# smps_test.net
KiCad netlist of a schematic drawn in EAGLE
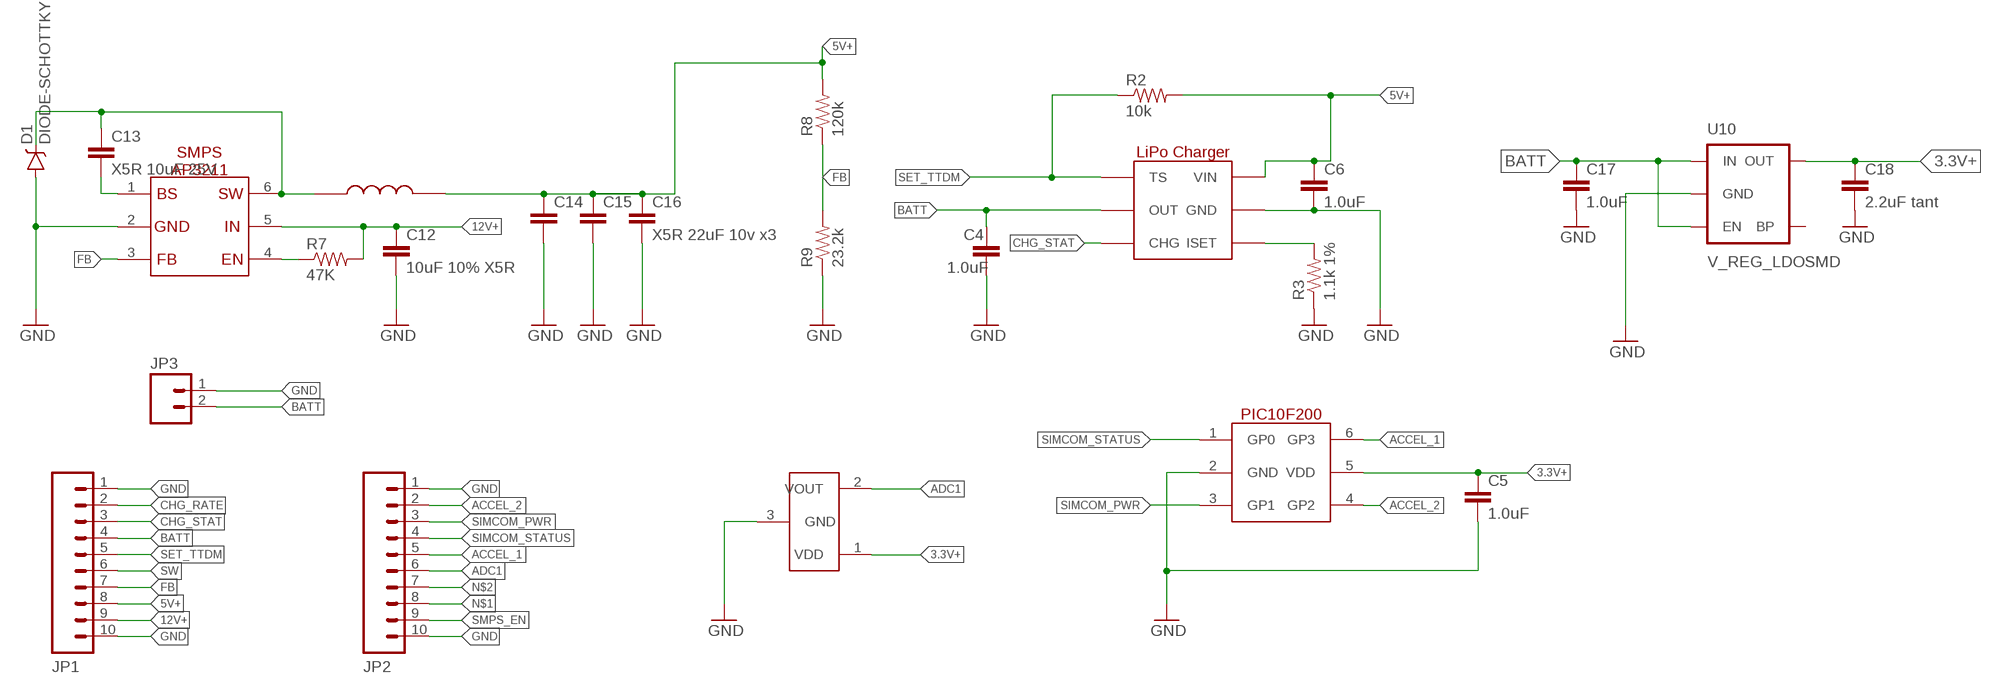
[diagram p0: schematic, sheet 1]

(export (version "E")
  (design (tool "Eeschema 10.0.6"))
  (components
    (comp (ref "C4")
      (value "1.0uF")
      (footprint "eagle-import:0603-CAP")
      (libsource (lib "eagle-import") (part "1.0UF-16V-10%(0603)"))
    )
    (comp (ref "C5")
      (value "1.0uF")
      (footprint "eagle-import:0603-CAP")
      (libsource (lib "eagle-import") (part "1.0UF-16V-10%(0603)"))
    )
    (comp (ref "C6")
      (value "1.0uF")
      (footprint "eagle-import:0603-CAP")
      (libsource (lib "eagle-import") (part "1.0UF-16V-10%(0603)"))
    )
    (comp (ref "C12")
      (value "10uF 10% X5R")
      (footprint "eagle-import:1206")
      (libsource (lib "eagle-import") (part "CAP1206"))
    )
    (comp (ref "C13")
      (value "X5R 10uF 25V")
      (footprint "eagle-import:0603-CAP")
      (libsource (lib "eagle-import") (part "CAP0603-CAP"))
    )
    (comp (ref "C14")
      (value "CAP0603-CAP")
      (footprint "eagle-import:0603-CAP")
      (libsource (lib "eagle-import") (part "CAP0603-CAP"))
    )
    (comp (ref "C15")
      (value "CAP0603-CAP")
      (footprint "eagle-import:0603-CAP")
      (libsource (lib "eagle-import") (part "CAP0603-CAP"))
    )
    (comp (ref "C16")
      (value "X5R 22uF 10v x3")
      (footprint "eagle-import:0603-CAP")
      (libsource (lib "eagle-import") (part "CAP0603-CAP"))
    )
    (comp (ref "C17")
      (value "1.0uF")
      (footprint "eagle-import:0603-CAP")
      (libsource (lib "eagle-import") (part "CAP0603-CAP"))
    )
    (comp (ref "C18")
      (value "2.2uF tant")
      (footprint "eagle-import:0603-CAP")
      (libsource (lib "eagle-import") (part "CAP0603-CAP"))
    )
    (comp (ref "D1")
      (value "DIODE-SCHOTTKY")
      (footprint "eagle-import:MICRO_SMP")
      (libsource (lib "eagle-import") (part "DIODE-SCHOTTKY"))
    )
    (comp (ref "JP1")
      (value "M10LOCK")
      (footprint "eagle-import:1X10_LOCK")
      (libsource (lib "eagle-import") (part "M10LOCK"))
    )
    (comp (ref "JP2")
      (value "M10LOCK")
      (footprint "eagle-import:1X10_LOCK")
      (libsource (lib "eagle-import") (part "M10LOCK"))
    )
    (comp (ref "JP3")
      (value "M02-JST-2MM-SMT")
      (footprint "eagle-import:JST-2-SMD")
      (libsource (lib "eagle-import") (part "M02-JST-2MM-SMT"))
    )
    (comp (ref "R2")
      (value "10k")
      (footprint "eagle-import:0603-RES")
      (libsource (lib "eagle-import") (part "RESISTOR0603-RES"))
    )
    (comp (ref "R3")
      (value "1.1k 1%")
      (footprint "eagle-import:0603-RES")
      (libsource (lib "eagle-import") (part "RESISTOR0603-RES"))
    )
    (comp (ref "R7")
      (value "47K")
      (footprint "eagle-import:0603-RES")
      (libsource (lib "eagle-import") (part "47KOHM1/10W1%(0603)"))
    )
    (comp (ref "R8")
      (value "120k")
      (footprint "eagle-import:0603-RES")
      (libsource (lib "eagle-import") (part "RESISTOR0603"))
    )
    (comp (ref "R9")
      (value "23.2k")
      (footprint "eagle-import:0603-RES")
      (libsource (lib "eagle-import") (part "RESISTOR0603"))
    )
    (comp (ref "U$1")
      (value "MCP9700T-E")
      (footprint "eagle-import:SOT23-3")
      (libsource (lib "eagle-import") (part "MCP9700T-E"))
    )
    (comp (ref "U$2")
      (value "AP3211")
      (footprint "eagle-import:SOT23-6")
      (libsource (lib "eagle-import") (part "AP3211"))
    )
    (comp (ref "U$4")
      (value "INDUCTOR")
      (footprint "eagle-import:INDUCTOR_FIXED")
      (libsource (lib "eagle-import") (part "INDUCTOR"))
    )
    (comp (ref "U3")
      (value "BQ21040")
      (footprint "eagle-import:SOT23-6")
      (libsource (lib "eagle-import") (part "BQ21040"))
    )
    (comp (ref "U6")
      (value "PIC10F200")
      (footprint "eagle-import:SOT23-6")
      (libsource (lib "eagle-import") (part "PIC10F200"))
    )
    (comp (ref "U10")
      (value "V_REG_LDOSMD")
      (footprint "eagle-import:SOT23-5")
      (libsource (lib "eagle-import") (part "V_REG_LDOSMD"))
    )
  )
  (nets
    (net (code "1") (name "3.3V+") (class "Default")
      (node (ref "C18") (pin "1") (pinfunction "1_1") (pintype "passive"))
      (node (ref "C5") (pin "1") (pinfunction "1_1") (pintype "passive"))
      (node (ref "U$1") (pin "1") (pinfunction "VDD_1") (pintype "bidirectional"))
      (node (ref "U10") (pin "5") (pinfunction "OUT_5") (pintype "passive"))
      (node (ref "U6") (pin "5") (pinfunction "VDD_5") (pintype "bidirectional"))
    )
    (net (code "2") (name "5V+") (class "Default")
      (node (ref "C14") (pin "1") (pinfunction "1_1") (pintype "passive"))
      (node (ref "C15") (pin "1") (pinfunction "1_1") (pintype "passive"))
      (node (ref "C16") (pin "1") (pinfunction "1_1") (pintype "passive"))
      (node (ref "C6") (pin "1") (pinfunction "1_1") (pintype "passive"))
      (node (ref "JP1") (pin "8") (pinfunction "8_8") (pintype "passive"))
      (node (ref "R2") (pin "2") (pinfunction "2_2") (pintype "passive"))
      (node (ref "R8") (pin "2") (pinfunction "2_2") (pintype "passive"))
      (node (ref "U$4") (pin "P$2") (pinfunction "P$2_P$2") (pintype "bidirectional"))
      (node (ref "U3") (pin "6") (pinfunction "VIN_6") (pintype "bidirectional"))
    )
    (net (code "3") (name "12V+") (class "Default")
      (node (ref "C12") (pin "1") (pinfunction "1_1") (pintype "passive"))
      (node (ref "JP1") (pin "9") (pinfunction "9_9") (pintype "passive"))
      (node (ref "R7") (pin "2") (pinfunction "2_2") (pintype "passive"))
      (node (ref "U$2") (pin "5") (pinfunction "P$5_5") (pintype "bidirectional"))
    )
    (net (code "4") (name "ACCEL_1") (class "Default")
      (node (ref "JP2") (pin "5") (pinfunction "5_5") (pintype "passive"))
      (node (ref "U6") (pin "6") (pinfunction "GP3_6") (pintype "bidirectional"))
    )
    (net (code "5") (name "ACCEL_2") (class "Default")
      (node (ref "JP2") (pin "2") (pinfunction "2_2") (pintype "passive"))
      (node (ref "U6") (pin "4") (pinfunction "GP2_4") (pintype "bidirectional"))
    )
    (net (code "6") (name "ADC1") (class "Default")
      (node (ref "JP2") (pin "6") (pinfunction "6_6") (pintype "passive"))
      (node (ref "U$1") (pin "2") (pinfunction "VOUT_2") (pintype "bidirectional"))
    )
    (net (code "7") (name "BATT") (class "Default")
      (node (ref "C17") (pin "1") (pinfunction "1_1") (pintype "passive"))
      (node (ref "C4") (pin "1") (pinfunction "1_1") (pintype "passive"))
      (node (ref "JP1") (pin "4") (pinfunction "4_4") (pintype "passive"))
      (node (ref "JP3") (pin "2") (pinfunction "1_2") (pintype "passive"))
      (node (ref "U10") (pin "1") (pinfunction "IN_1") (pintype "input"))
      (node (ref "U10") (pin "3") (pinfunction "EN_3") (pintype "input"))
      (node (ref "U3") (pin "2") (pinfunction "OUT_2") (pintype "bidirectional"))
    )
    (net (code "8") (name "CHG_RATE") (class "Default")
      (node (ref "JP1") (pin "2") (pinfunction "2_2") (pintype "passive"))
      (node (ref "R3") (pin "2") (pinfunction "2_2") (pintype "passive"))
      (node (ref "U3") (pin "4") (pinfunction "ISET_4") (pintype "bidirectional"))
    )
    (net (code "9") (name "CHG_STAT") (class "Default")
      (node (ref "JP1") (pin "3") (pinfunction "3_3") (pintype "passive"))
      (node (ref "U3") (pin "3") (pinfunction "CHG_3") (pintype "bidirectional"))
    )
    (net (code "10") (name "FB") (class "Default")
      (node (ref "JP1") (pin "7") (pinfunction "7_7") (pintype "passive"))
      (node (ref "R8") (pin "1") (pinfunction "1_1") (pintype "passive"))
      (node (ref "R9") (pin "2") (pinfunction "2_2") (pintype "passive"))
      (node (ref "U$2") (pin "3") (pinfunction "P$3_3") (pintype "bidirectional"))
    )
    (net (code "11") (name "GND") (class "Default")
      (node (ref "C12") (pin "2") (pinfunction "2_2") (pintype "passive"))
      (node (ref "C14") (pin "2") (pinfunction "2_2") (pintype "passive"))
      (node (ref "C15") (pin "2") (pinfunction "2_2") (pintype "passive"))
      (node (ref "C16") (pin "2") (pinfunction "2_2") (pintype "passive"))
      (node (ref "C17") (pin "2") (pinfunction "2_2") (pintype "passive"))
      (node (ref "C18") (pin "2") (pinfunction "2_2") (pintype "passive"))
      (node (ref "C4") (pin "2") (pinfunction "2_2") (pintype "passive"))
      (node (ref "C5") (pin "2") (pinfunction "2_2") (pintype "passive"))
      (node (ref "C6") (pin "2") (pinfunction "2_2") (pintype "passive"))
      (node (ref "D1") (pin "P$2") (pinfunction "A_P$2") (pintype "passive"))
      (node (ref "JP1") (pin "1") (pinfunction "1_1") (pintype "passive"))
      (node (ref "JP1") (pin "10") (pinfunction "10_10") (pintype "passive"))
      (node (ref "JP2") (pin "1") (pinfunction "1_1") (pintype "passive"))
      (node (ref "JP2") (pin "10") (pinfunction "10_10") (pintype "passive"))
      (node (ref "JP3") (pin "1") (pinfunction "2_1") (pintype "passive"))
      (node (ref "R3") (pin "1") (pinfunction "1_1") (pintype "passive"))
      (node (ref "R9") (pin "1") (pinfunction "1_1") (pintype "passive"))
      (node (ref "U$1") (pin "3") (pinfunction "GND_3") (pintype "bidirectional"))
      (node (ref "U$2") (pin "2") (pinfunction "P$2_2") (pintype "bidirectional"))
      (node (ref "U10") (pin "2") (pinfunction "GND_2") (pintype "input"))
      (node (ref "U3") (pin "5") (pinfunction "GND_5") (pintype "bidirectional"))
      (node (ref "U6") (pin "2") (pinfunction "GND_2") (pintype "bidirectional"))
    )
    (net (code "12") (name "N$1") (class "Default")
      (node (ref "JP2") (pin "8") (pinfunction "8_8") (pintype "passive"))
    )
    (net (code "13") (name "N$2") (class "Default")
      (node (ref "JP2") (pin "7") (pinfunction "7_7") (pintype "passive"))
    )
    (net (code "14") (name "Net-(U$2-P$1)") (class "Default")
      (node (ref "C13") (pin "2") (pinfunction "2_2") (pintype "passive"))
      (node (ref "U$2") (pin "1") (pinfunction "P$1_1") (pintype "bidirectional"))
    )
    (net (code "15") (name "SET_TTDM") (class "Default")
      (node (ref "JP1") (pin "5") (pinfunction "5_5") (pintype "passive"))
      (node (ref "R2") (pin "1") (pinfunction "1_1") (pintype "passive"))
      (node (ref "U3") (pin "1") (pinfunction "TS_1") (pintype "bidirectional"))
    )
    (net (code "16") (name "SIMCOM_PWR") (class "Default")
      (node (ref "JP2") (pin "3") (pinfunction "3_3") (pintype "passive"))
      (node (ref "U6") (pin "3") (pinfunction "GP1_3") (pintype "bidirectional"))
    )
    (net (code "17") (name "SIMCOM_STATUS") (class "Default")
      (node (ref "JP2") (pin "4") (pinfunction "4_4") (pintype "passive"))
      (node (ref "U6") (pin "1") (pinfunction "GP0_1") (pintype "bidirectional"))
    )
    (net (code "18") (name "SMPS_EN") (class "Default")
      (node (ref "JP2") (pin "9") (pinfunction "9_9") (pintype "passive"))
      (node (ref "R7") (pin "1") (pinfunction "1_1") (pintype "passive"))
      (node (ref "U$2") (pin "4") (pinfunction "P$4_4") (pintype "bidirectional"))
    )
    (net (code "19") (name "SW") (class "Default")
      (node (ref "C13") (pin "1") (pinfunction "1_1") (pintype "passive"))
      (node (ref "D1") (pin "P$1") (pinfunction "C_P$1") (pintype "passive"))
      (node (ref "JP1") (pin "6") (pinfunction "6_6") (pintype "passive"))
      (node (ref "U$2") (pin "6") (pinfunction "P$6_6") (pintype "bidirectional"))
      (node (ref "U$4") (pin "P$1") (pinfunction "P$1_P$1") (pintype "bidirectional"))
    )
    (net (code "20") (name "unconnected-(U10-BP-Pad4)") (class "Default")
      (node (ref "U10") (pin "4") (pinfunction "BP_4") (pintype "input"))
    )
  )
)
